# lab3-1.net
KiCad netlist of a schematic drawn in EAGLE
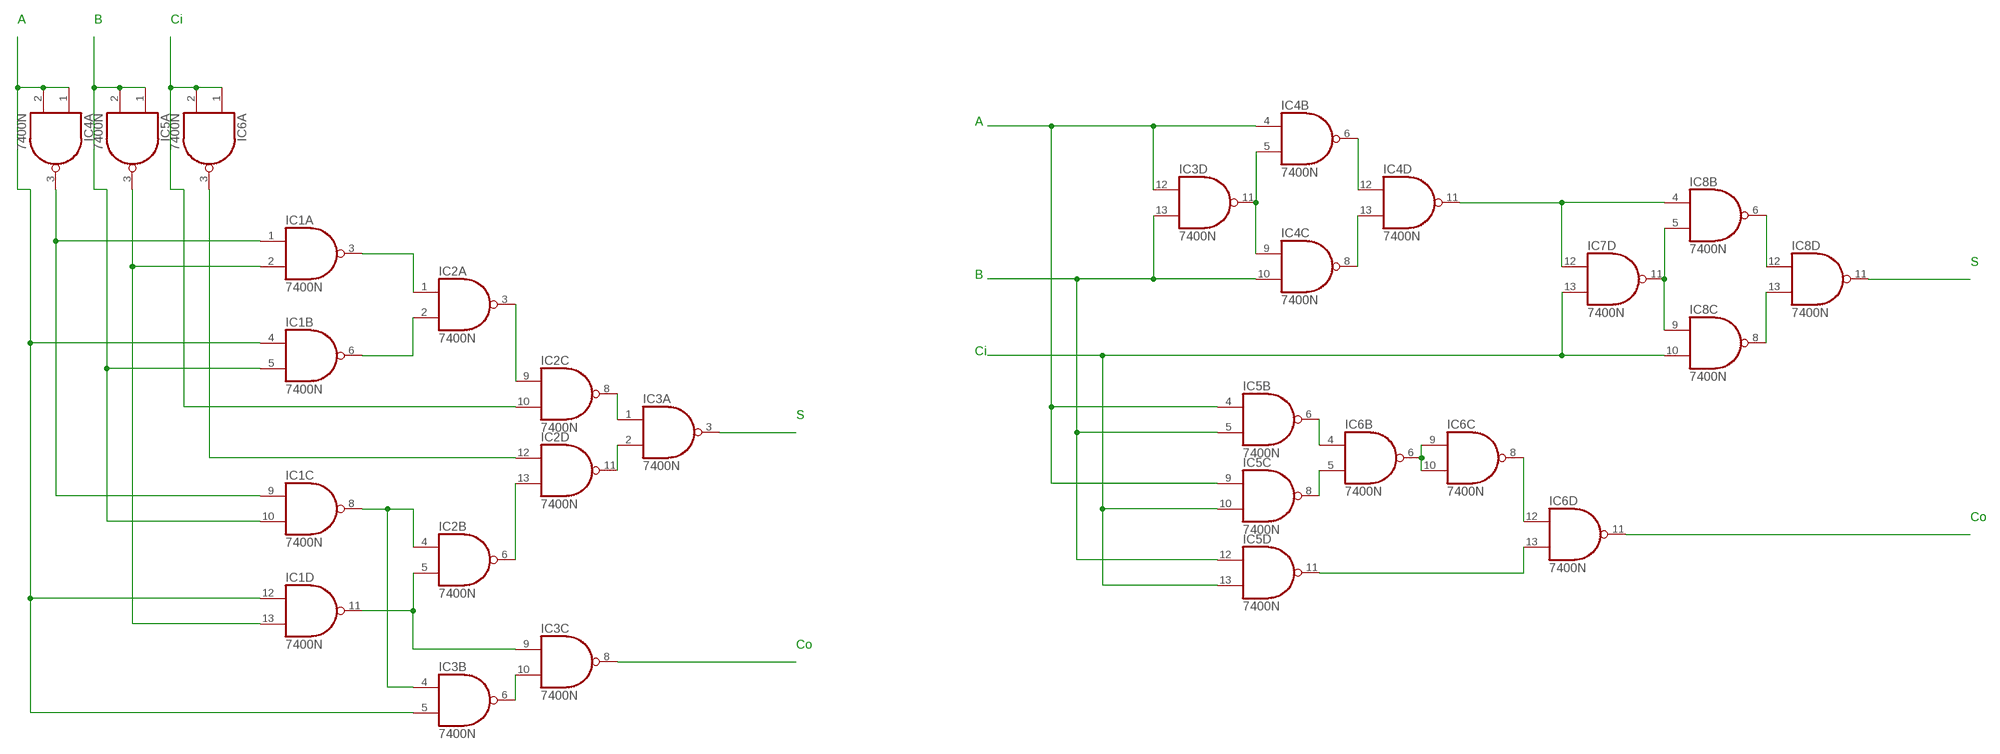
[diagram p0: schematic, sheet 1]

(export (version "E")
  (design (tool "Eeschema 10.0.6"))
  (components
    (comp (ref "IC1")
      (value "7400N")
      (footprint "eagle-import:DIL14")
      (libsource (lib "eagle-import") (part "7400N"))
    )
    (comp (ref "IC2")
      (value "7400N")
      (footprint "eagle-import:DIL14")
      (libsource (lib "eagle-import") (part "7400N"))
    )
    (comp (ref "IC3")
      (value "7400N")
      (footprint "eagle-import:DIL14")
      (libsource (lib "eagle-import") (part "7400N"))
    )
    (comp (ref "IC4")
      (value "7400N")
      (footprint "eagle-import:DIL14")
      (libsource (lib "eagle-import") (part "7400N"))
    )
    (comp (ref "IC5")
      (value "7400N")
      (footprint "eagle-import:DIL14")
      (libsource (lib "eagle-import") (part "7400N"))
    )
    (comp (ref "IC6")
      (value "7400N")
      (footprint "eagle-import:DIL14")
      (libsource (lib "eagle-import") (part "7400N"))
    )
    (comp (ref "IC7")
      (value "7400N")
      (footprint "eagle-import:DIL14")
      (libsource (lib "eagle-import") (part "7400N"))
    )
    (comp (ref "IC8")
      (value "7400N")
      (footprint "eagle-import:DIL14")
      (libsource (lib "eagle-import") (part "7400N"))
    )
  )
  (nets
    (net (code "1") (name "Net-(IC1A-I0)") (class "Default")
      (node (ref "IC1") (pin "1") (pinfunction "I0_1") (pintype "input"))
      (node (ref "IC1") (pin "9") (pinfunction "I0_9") (pintype "input"))
      (node (ref "IC4") (pin "3") (pinfunction "O_3") (pintype "output"))
    )
    (net (code "2") (name "Net-(IC1A-I1)") (class "Default")
      (node (ref "IC1") (pin "13") (pinfunction "I1_13") (pintype "input"))
      (node (ref "IC1") (pin "2") (pinfunction "I1_2") (pintype "input"))
      (node (ref "IC5") (pin "3") (pinfunction "O_3") (pintype "output"))
    )
    (net (code "3") (name "Net-(IC1A-O)") (class "Default")
      (node (ref "IC1") (pin "3") (pinfunction "O_3") (pintype "output"))
      (node (ref "IC2") (pin "1") (pinfunction "I0_1") (pintype "input"))
    )
    (net (code "4") (name "Net-(IC1B-I0)") (class "Default")
      (node (ref "IC1") (pin "12") (pinfunction "I0_12") (pintype "input"))
      (node (ref "IC1") (pin "4") (pinfunction "I0_4") (pintype "input"))
      (node (ref "IC3") (pin "5") (pinfunction "I1_5") (pintype "input"))
      (node (ref "IC4") (pin "1") (pinfunction "I0_1") (pintype "input"))
      (node (ref "IC4") (pin "2") (pinfunction "I1_2") (pintype "input"))
    )
    (net (code "5") (name "Net-(IC1B-I1)") (class "Default")
      (node (ref "IC1") (pin "10") (pinfunction "I1_10") (pintype "input"))
      (node (ref "IC1") (pin "5") (pinfunction "I1_5") (pintype "input"))
      (node (ref "IC5") (pin "1") (pinfunction "I0_1") (pintype "input"))
      (node (ref "IC5") (pin "2") (pinfunction "I1_2") (pintype "input"))
    )
    (net (code "6") (name "Net-(IC1B-O)") (class "Default")
      (node (ref "IC1") (pin "6") (pinfunction "O_6") (pintype "output"))
      (node (ref "IC2") (pin "2") (pinfunction "I1_2") (pintype "input"))
    )
    (net (code "7") (name "Net-(IC1C-O)") (class "Default")
      (node (ref "IC1") (pin "8") (pinfunction "O_8") (pintype "output"))
      (node (ref "IC2") (pin "4") (pinfunction "I0_4") (pintype "input"))
      (node (ref "IC3") (pin "4") (pinfunction "I0_4") (pintype "input"))
    )
    (net (code "8") (name "Net-(IC1D-O)") (class "Default")
      (node (ref "IC1") (pin "11") (pinfunction "O_11") (pintype "output"))
      (node (ref "IC2") (pin "5") (pinfunction "I1_5") (pintype "input"))
      (node (ref "IC3") (pin "9") (pinfunction "I0_9") (pintype "input"))
    )
    (net (code "9") (name "Net-(IC2A-O)") (class "Default")
      (node (ref "IC2") (pin "3") (pinfunction "O_3") (pintype "output"))
      (node (ref "IC2") (pin "9") (pinfunction "I0_9") (pintype "input"))
    )
    (net (code "10") (name "Net-(IC2B-O)") (class "Default")
      (node (ref "IC2") (pin "13") (pinfunction "I1_13") (pintype "input"))
      (node (ref "IC2") (pin "6") (pinfunction "O_6") (pintype "output"))
    )
    (net (code "11") (name "Net-(IC2C-I1)") (class "Default")
      (node (ref "IC2") (pin "10") (pinfunction "I1_10") (pintype "input"))
      (node (ref "IC6") (pin "1") (pinfunction "I0_1") (pintype "input"))
      (node (ref "IC6") (pin "2") (pinfunction "I1_2") (pintype "input"))
    )
    (net (code "12") (name "Net-(IC2C-O)") (class "Default")
      (node (ref "IC2") (pin "8") (pinfunction "O_8") (pintype "output"))
      (node (ref "IC3") (pin "1") (pinfunction "I0_1") (pintype "input"))
    )
    (net (code "13") (name "Net-(IC2D-I0)") (class "Default")
      (node (ref "IC2") (pin "12") (pinfunction "I0_12") (pintype "input"))
      (node (ref "IC6") (pin "3") (pinfunction "O_3") (pintype "output"))
    )
    (net (code "14") (name "Net-(IC2D-O)") (class "Default")
      (node (ref "IC2") (pin "11") (pinfunction "O_11") (pintype "output"))
      (node (ref "IC3") (pin "2") (pinfunction "I1_2") (pintype "input"))
    )
    (net (code "15") (name "Net-(IC3B-O)") (class "Default")
      (node (ref "IC3") (pin "10") (pinfunction "I1_10") (pintype "input"))
      (node (ref "IC3") (pin "6") (pinfunction "O_6") (pintype "output"))
    )
    (net (code "16") (name "Net-(IC3D-I0)") (class "Default")
      (node (ref "IC3") (pin "12") (pinfunction "I0_12") (pintype "input"))
      (node (ref "IC4") (pin "4") (pinfunction "I0_4") (pintype "input"))
      (node (ref "IC5") (pin "4") (pinfunction "I0_4") (pintype "input"))
      (node (ref "IC5") (pin "9") (pinfunction "I0_9") (pintype "input"))
    )
    (net (code "17") (name "Net-(IC3D-I1)") (class "Default")
      (node (ref "IC3") (pin "13") (pinfunction "I1_13") (pintype "input"))
      (node (ref "IC4") (pin "10") (pinfunction "I1_10") (pintype "input"))
      (node (ref "IC5") (pin "12") (pinfunction "I0_12") (pintype "input"))
      (node (ref "IC5") (pin "5") (pinfunction "I1_5") (pintype "input"))
    )
    (net (code "18") (name "Net-(IC3D-O)") (class "Default")
      (node (ref "IC3") (pin "11") (pinfunction "O_11") (pintype "output"))
      (node (ref "IC4") (pin "5") (pinfunction "I1_5") (pintype "input"))
      (node (ref "IC4") (pin "9") (pinfunction "I0_9") (pintype "input"))
    )
    (net (code "19") (name "Net-(IC4B-O)") (class "Default")
      (node (ref "IC4") (pin "12") (pinfunction "I0_12") (pintype "input"))
      (node (ref "IC4") (pin "6") (pinfunction "O_6") (pintype "output"))
    )
    (net (code "20") (name "Net-(IC4C-O)") (class "Default")
      (node (ref "IC4") (pin "13") (pinfunction "I1_13") (pintype "input"))
      (node (ref "IC4") (pin "8") (pinfunction "O_8") (pintype "output"))
    )
    (net (code "21") (name "Net-(IC4D-O)") (class "Default")
      (node (ref "IC4") (pin "11") (pinfunction "O_11") (pintype "output"))
      (node (ref "IC7") (pin "12") (pinfunction "I0_12") (pintype "input"))
      (node (ref "IC8") (pin "4") (pinfunction "I0_4") (pintype "input"))
    )
    (net (code "22") (name "Net-(IC5B-O)") (class "Default")
      (node (ref "IC5") (pin "6") (pinfunction "O_6") (pintype "output"))
      (node (ref "IC6") (pin "4") (pinfunction "I0_4") (pintype "input"))
    )
    (net (code "23") (name "Net-(IC5C-I1)") (class "Default")
      (node (ref "IC5") (pin "10") (pinfunction "I1_10") (pintype "input"))
      (node (ref "IC5") (pin "13") (pinfunction "I1_13") (pintype "input"))
      (node (ref "IC7") (pin "13") (pinfunction "I1_13") (pintype "input"))
      (node (ref "IC8") (pin "10") (pinfunction "I1_10") (pintype "input"))
    )
    (net (code "24") (name "Net-(IC5C-O)") (class "Default")
      (node (ref "IC5") (pin "8") (pinfunction "O_8") (pintype "output"))
      (node (ref "IC6") (pin "5") (pinfunction "I1_5") (pintype "input"))
    )
    (net (code "25") (name "Net-(IC5D-O)") (class "Default")
      (node (ref "IC5") (pin "11") (pinfunction "O_11") (pintype "output"))
      (node (ref "IC6") (pin "13") (pinfunction "I1_13") (pintype "input"))
    )
    (net (code "26") (name "Net-(IC6B-O)") (class "Default")
      (node (ref "IC6") (pin "10") (pinfunction "I1_10") (pintype "input"))
      (node (ref "IC6") (pin "6") (pinfunction "O_6") (pintype "output"))
      (node (ref "IC6") (pin "9") (pinfunction "I0_9") (pintype "input"))
    )
    (net (code "27") (name "Net-(IC6C-O)") (class "Default")
      (node (ref "IC6") (pin "12") (pinfunction "I0_12") (pintype "input"))
      (node (ref "IC6") (pin "8") (pinfunction "O_8") (pintype "output"))
    )
    (net (code "28") (name "Net-(IC7D-O)") (class "Default")
      (node (ref "IC7") (pin "11") (pinfunction "O_11") (pintype "output"))
      (node (ref "IC8") (pin "5") (pinfunction "I1_5") (pintype "input"))
      (node (ref "IC8") (pin "9") (pinfunction "I0_9") (pintype "input"))
    )
    (net (code "29") (name "Net-(IC8B-O)") (class "Default")
      (node (ref "IC8") (pin "12") (pinfunction "I0_12") (pintype "input"))
      (node (ref "IC8") (pin "6") (pinfunction "O_6") (pintype "output"))
    )
    (net (code "30") (name "Net-(IC8C-O)") (class "Default")
      (node (ref "IC8") (pin "13") (pinfunction "I1_13") (pintype "input"))
      (node (ref "IC8") (pin "8") (pinfunction "O_8") (pintype "output"))
    )
    (net (code "31") (name "unconnected-(IC3A-O-Pad3)") (class "Default")
      (node (ref "IC3") (pin "3") (pinfunction "O_3") (pintype "output"))
    )
    (net (code "32") (name "unconnected-(IC3C-O-Pad8)") (class "Default")
      (node (ref "IC3") (pin "8") (pinfunction "O_8") (pintype "output"))
    )
    (net (code "33") (name "unconnected-(IC6D-O-Pad11)") (class "Default")
      (node (ref "IC6") (pin "11") (pinfunction "O_11") (pintype "output"))
    )
    (net (code "34") (name "unconnected-(IC8D-O-Pad11)") (class "Default")
      (node (ref "IC8") (pin "11") (pinfunction "O_11") (pintype "output"))
    )
  )
)
